# Storage.net
KiCad netlist of a schematic drawn in Altium Designer
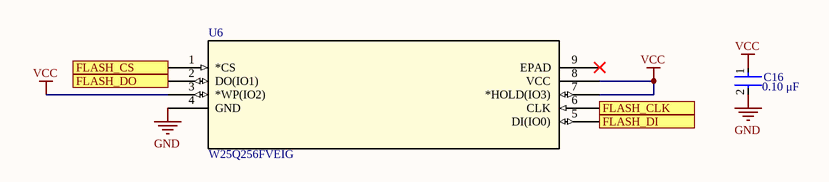
[diagram p0: Storage.SchDoc]

(export (version "E")
  (design (tool "Eeschema 10.0.6"))
  (components
    (comp (ref "C16")
      (value "C0603C104K5RACTU")
      (footprint "FP-C0603C-CF-MFG")
      (description "CAP CER 0.1UF 50V X7R 0603")
      (fields
        (field (name "TOLERANCE") "0.1")
        (field (name "MANUFACTURER") "KEMET")
        (field (name "CAPACITANCE") "0.10 μF")
      )
      (libsource (lib "Altium Content Vault") (part "b4654b650e69147ec39a6b967a45e02"))
    )
    (comp (ref "U6")
      (value "W25Q256FVEIG")
      (footprint "WIN_E-8_WIN")
      (description "No Description Available")
      (fields (field (name "COPYRIGHT") "Copyright (C) 2022 Ultra Librarian. All rights reserved."))
      (libsource (lib "W25Q256FVEIG") (part "W25Q256FVEIG"))
    )
  )
  (nets
    (net (code "1") (name "/FLASH_CLK") (class "Default")
      (node (ref "U6") (pin "6") (pinfunction "CLK_6") (pintype "input"))
    )
    (net (code "2") (name "/FLASH_CS") (class "Default")
      (node (ref "U6") (pin "1") (pinfunction "*CS_1") (pintype "input"))
    )
    (net (code "3") (name "/FLASH_DI") (class "Default")
      (node (ref "U6") (pin "5") (pinfunction "DI(IO0)_5") (pintype "bidirectional"))
    )
    (net (code "4") (name "/FLASH_DO") (class "Default")
      (node (ref "U6") (pin "2") (pinfunction "DO(IO1)_2") (pintype "bidirectional"))
    )
    (net (code "5") (name "GND") (class "Default")
      (node (ref "C16") (pin "2") (pinfunction "2_2") (pintype "passive"))
      (node (ref "U6") (pin "4") (pinfunction "GND_4") (pintype "power_in"))
    )
    (net (code "6") (name "VCC") (class "Default")
      (node (ref "C16") (pin "1") (pinfunction "1_1") (pintype "passive"))
      (node (ref "U6") (pin "3") (pinfunction "*WP(IO2)_3") (pintype "bidirectional"))
      (node (ref "U6") (pin "7") (pinfunction "*HOLD(IO3)_7") (pintype "bidirectional"))
      (node (ref "U6") (pin "8") (pinfunction "VCC_8") (pintype "power_in"))
    )
    (net (code "7") (name "unconnected-(U6-EPAD-Pad9)") (class "Default")
      (node (ref "U6") (pin "9") (pinfunction "EPAD_9") (pintype "passive+no_connect"))
    )
  )
)
